# V1_0.net
KiCad netlist of a schematic drawn in Altium Designer
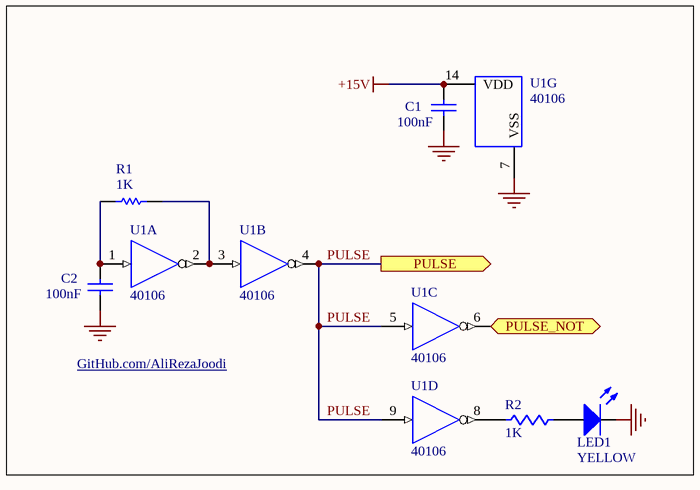
[diagram p0: V1.0.SchDoc]

(export (version "E")
  (design (tool "Eeschema 10.0.6"))
  (components
    (comp (ref "C1")
      (value "100nF")
      (footprint "CAPNTO2.54-3.05x1.78A")
      (description "Capacitor")
      (fields (field (name "MANUFACTURER") "Generic Components") (field (name "PUBLISHER") "Altium Limited"))
      (libsource (lib "Miscellaneous Devices") (part "Cap"))
    )
    (comp (ref "C2")
      (value "100nF")
      (footprint "CAPNTO5.08-7.37x3.94")
      (description "Capacitor")
      (fields (field (name "PUBLISHER") "Altium Limited"))
      (libsource (lib "Miscellaneous Devices") (part "Cap"))
    )
    (comp (ref "LED1")
      (value "YELLOW")
      (footprint "LED-5mm_Red")
      (description "Typical INFRARED GaAs LED")
      (fields (field (name "MANUFACTURER") "Generic Components") (field (name "PUBLISHER") "Altium Limited"))
      (libsource (lib "Miscellaneous Devices") (part "LED"))
    )
    (comp (ref "R1")
      (value "1K")
      (footprint "AXIAL-0.4")
      (description "Resistor")
      (fields (field (name "PUBLISHER") "Altium Limited"))
      (libsource (lib "") (part "Res1_1"))
    )
    (comp (ref "R2")
      (value "1K")
      (footprint "AXIAL-0.4")
      (description "Resistor")
      (fields (field (name "MANUFACTURER") "Generic Components") (field (name "PUBLISHER") "Altium Limited"))
      (libsource (lib "Miscellaneous Devices") (part "Res1"))
    )
    (comp (ref "U1")
      (value "40106")
      (footprint "DIP14")
      (description "Hex inverting Schmitt trigger, 14-Pin")
      (fields (field (name "PUBLISHER") "Altium Limited"))
      (libsource (lib "my Libraries") (part "40106"))
    )
  )
  (nets
    (net (code "1") (name "+15V") (class "Default")
      (node (ref "C1") (pin "2") (pinfunction "2_2") (pintype "passive"))
      (node (ref "U1") (pin "14") (pinfunction "VDD_14") (pintype "passive"))
    )
    (net (code "2") (name "/PULSE") (class "Default")
      (node (ref "U1") (pin "4") (pinfunction "~{O}_4") (pintype "output"))
      (node (ref "U1") (pin "5") (pinfunction "I_5") (pintype "input"))
      (node (ref "U1") (pin "9") (pinfunction "I_9") (pintype "input"))
    )
    (net (code "3") (name "/PULSE_NOT") (class "Default")
      (node (ref "U1") (pin "6") (pinfunction "~{O}_6") (pintype "output"))
    )
    (net (code "4") (name "GND") (class "Default")
      (node (ref "C1") (pin "1") (pinfunction "1_1") (pintype "passive"))
      (node (ref "C2") (pin "1") (pinfunction "1_1") (pintype "passive"))
      (node (ref "LED1") (pin "2") (pinfunction "K_2") (pintype "passive"))
      (node (ref "U1") (pin "7") (pinfunction "VSS_7") (pintype "power_in"))
    )
    (net (code "5") (name "Net-(LED1-A)") (class "Default")
      (node (ref "LED1") (pin "1") (pinfunction "A_1") (pintype "passive"))
      (node (ref "R2") (pin "2") (pinfunction "2_2") (pintype "passive"))
    )
    (net (code "6") (name "Net-(U1A-I)") (class "Default")
      (node (ref "C2") (pin "2") (pinfunction "2_2") (pintype "passive"))
      (node (ref "R1") (pin "2") (pinfunction "2_2") (pintype "passive"))
      (node (ref "U1") (pin "1") (pinfunction "I_1") (pintype "input"))
    )
    (net (code "7") (name "Net-(U1A-~{O})") (class "Default")
      (node (ref "R1") (pin "1") (pinfunction "1_1") (pintype "passive"))
      (node (ref "U1") (pin "2") (pinfunction "~{O}_2") (pintype "output"))
      (node (ref "U1") (pin "3") (pinfunction "I_3") (pintype "input"))
    )
    (net (code "8") (name "Net-(U1D-~{O})") (class "Default")
      (node (ref "R2") (pin "1") (pinfunction "1_1") (pintype "passive"))
      (node (ref "U1") (pin "8") (pinfunction "~{O}_8") (pintype "output"))
    )
  )
)
